# Sheet4.net
KiCad netlist of a schematic drawn in Altium Designer
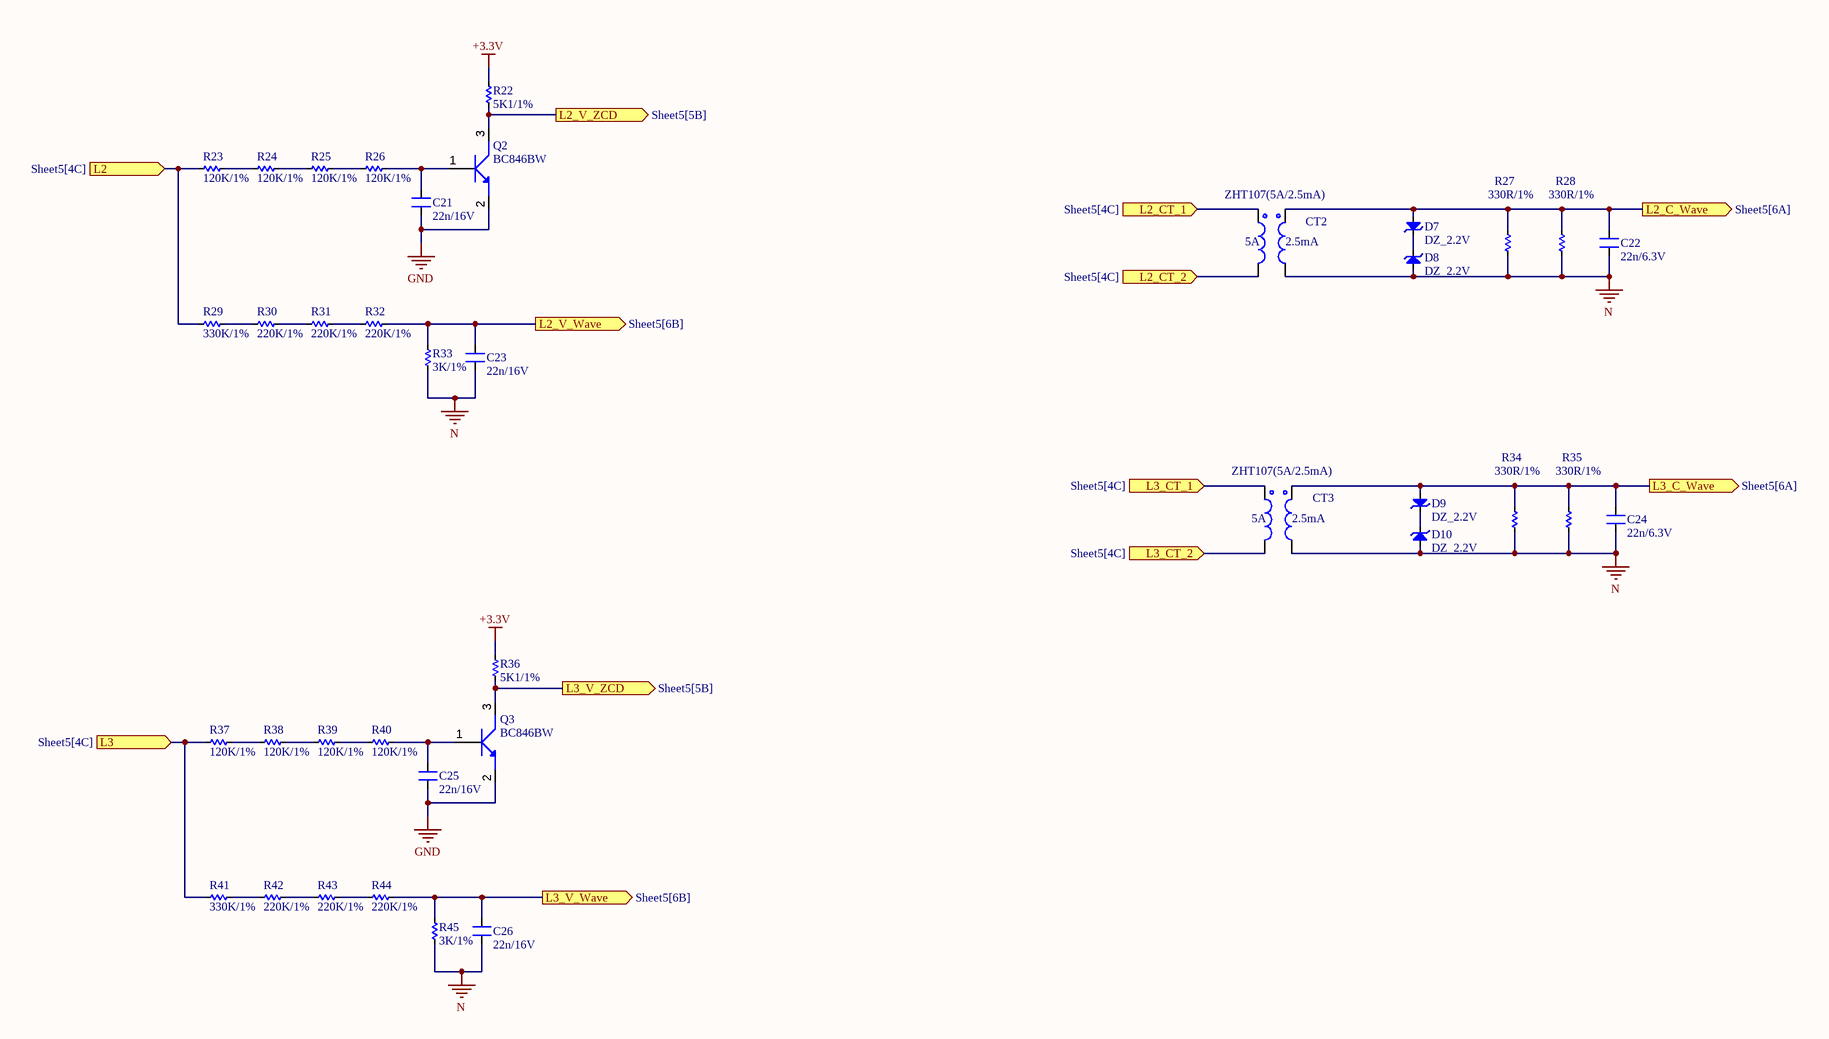
[diagram p0: Sheet4.SchDoc]

(export (version "E")
  (design (tool "Eeschema 10.0.6"))
  (components
    (comp (ref "C21")
      (value "22n/16V")
      (footprint "CAP_C_2012X110")
      (libsource (lib "DAK_Altium_Integrated_Lib") (part "CAP_SMD"))
    )
    (comp (ref "C22")
      (value "22n/6.3V")
      (footprint "CAP_C_2012X110")
      (libsource (lib "DAK_Altium_Integrated_Lib") (part "CAP_SMD"))
    )
    (comp (ref "C23")
      (value "22n/16V")
      (footprint "CAP_C_2012X110")
      (libsource (lib "DAK_Altium_Integrated_Lib") (part "CAP_SMD"))
    )
    (comp (ref "C24")
      (value "22n/6.3V")
      (footprint "CAP_C_2012X110")
      (libsource (lib "DAK_Altium_Integrated_Lib") (part "CAP_SMD"))
    )
    (comp (ref "C25")
      (value "22n/16V")
      (footprint "CAP_C_2012X110")
      (libsource (lib "DAK_Altium_Integrated_Lib") (part "CAP_SMD"))
    )
    (comp (ref "C26")
      (value "22n/16V")
      (footprint "CAP_C_2012X110")
      (libsource (lib "DAK_Altium_Integrated_Lib") (part "CAP_SMD"))
    )
    (comp (ref "CT2")
      (value "ZHT107(5A/2.5mA)")
      (footprint "ZHT107")
      (description "C5183046")
      (libsource (lib "PowerMeter") (part "ZHT-107"))
    )
    (comp (ref "CT3")
      (value "ZHT107(5A/2.5mA)")
      (footprint "ZHT107")
      (description "C5183046")
      (libsource (lib "PowerMeter") (part "ZHT-107"))
    )
    (comp (ref "D7")
      (value "DZ_2.2V")
      (footprint "LL-34")
      (description "Zenner")
      (libsource (lib "PowerMeter") (part "DIODE Zener"))
    )
    (comp (ref "D8")
      (value "DZ_2.2V")
      (footprint "LL-34")
      (description "Zenner")
      (libsource (lib "PowerMeter") (part "DIODE Zener"))
    )
    (comp (ref "D9")
      (value "DZ_2.2V")
      (footprint "LL-34")
      (description "Zenner")
      (libsource (lib "PowerMeter") (part "DIODE Zener"))
    )
    (comp (ref "D10")
      (value "DZ_2.2V")
      (footprint "LL-34")
      (description "Zenner")
      (libsource (lib "PowerMeter") (part "DIODE Zener"))
    )
    (comp (ref "Q2") (value "BC846BW") (footprint "SOT-323") (libsource (lib "PowerMeter") (part "BJT_NPN")))
    (comp (ref "Q3") (value "BC846BW") (footprint "SOT-323") (libsource (lib "PowerMeter") (part "BJT_NPN")))
    (comp (ref "R22")
      (value "5K1/1%")
      (footprint "RES_C_2012X65")
      (description "Resistor")
      (fields
        (field (name "MANUFACTURER") "Generic Components")
        (field (name "LCSC PART #") "C26023")
        (field (name "PUBLISHER") "Altium Hobart Technology Centre")
      )
      (libsource (lib "Library") (part "Res-SMD"))
    )
    (comp (ref "R23")
      (value "120K/1%")
      (footprint "RES_C_3216X70")
      (description "Resistor")
      (fields
        (field (name "MANUFACTURER") "Generic Components")
        (field (name "LCSC PART #") "C17908")
        (field (name "PUBLISHER") "Altium Hobart Technology Centre")
      )
      (libsource (lib "Library") (part "Res-SMD"))
    )
    (comp (ref "R24")
      (value "120K/1%")
      (footprint "RES_C_3216X70")
      (description "Resistor")
      (fields
        (field (name "MANUFACTURER") "Generic Components")
        (field (name "LCSC PART #") "C17908")
        (field (name "PUBLISHER") "Altium Hobart Technology Centre")
      )
      (libsource (lib "Library") (part "Res-SMD"))
    )
    (comp (ref "R25")
      (value "120K/1%")
      (footprint "RES_C_3216X70")
      (description "Resistor")
      (fields
        (field (name "MANUFACTURER") "Generic Components")
        (field (name "LCSC PART #") "C17908")
        (field (name "PUBLISHER") "Altium Hobart Technology Centre")
      )
      (libsource (lib "Library") (part "Res-SMD"))
    )
    (comp (ref "R26")
      (value "120K/1%")
      (footprint "RES_C_3216X70")
      (description "Resistor")
      (fields
        (field (name "MANUFACTURER") "Generic Components")
        (field (name "LCSC PART #") "C17908")
        (field (name "PUBLISHER") "Altium Hobart Technology Centre")
      )
      (libsource (lib "Library") (part "Res-SMD"))
    )
    (comp (ref "R27")
      (value "330R/1%")
      (footprint "RES_C_3216X70")
      (description "Resistor")
      (fields
        (field (name "MANUFACTURER") "Generic Components")
        (field (name "LCSC PART #") "C912714")
        (field (name "PUBLISHER") "Altium Hobart Technology Centre")
      )
      (libsource (lib "Library") (part "Res-SMD"))
    )
    (comp (ref "R28")
      (value "330R/1%")
      (footprint "RES_C_3216X70")
      (description "Resistor")
      (fields
        (field (name "MANUFACTURER") "Generic Components")
        (field (name "LCSC PART #") "C912714")
        (field (name "PUBLISHER") "Altium Hobart Technology Centre")
      )
      (libsource (lib "Library") (part "Res-SMD"))
    )
    (comp (ref "R29")
      (value "330K/1%")
      (footprint "RES_C_3216X70")
      (description "Resistor")
      (fields
        (field (name "MANUFACTURER") "Generic Components")
        (field (name "LCSC PART #") "C17929")
        (field (name "PUBLISHER") "Altium Hobart Technology Centre")
      )
      (libsource (lib "Library") (part "Res-SMD"))
    )
    (comp (ref "R30")
      (value "220K/1%")
      (footprint "RES_C_3216X70")
      (description "Resistor")
      (fields
        (field (name "MANUFACTURER") "Generic Components")
        (field (name "LCSC PART #") "C17956")
        (field (name "PUBLISHER") "Altium Hobart Technology Centre")
      )
      (libsource (lib "Library") (part "Res-SMD"))
    )
    (comp (ref "R31")
      (value "220K/1%")
      (footprint "RES_C_3216X70")
      (description "Resistor")
      (fields
        (field (name "MANUFACTURER") "Generic Components")
        (field (name "LCSC PART #") "C17956")
        (field (name "PUBLISHER") "Altium Hobart Technology Centre")
      )
      (libsource (lib "Library") (part "Res-SMD"))
    )
    (comp (ref "R32")
      (value "220K/1%")
      (footprint "RES_C_3216X70")
      (description "Resistor")
      (fields
        (field (name "MANUFACTURER") "Generic Components")
        (field (name "LCSC PART #") "C17956")
        (field (name "PUBLISHER") "Altium Hobart Technology Centre")
      )
      (libsource (lib "Library") (part "Res-SMD"))
    )
    (comp (ref "R33")
      (value "3K/1%")
      (footprint "RES_C_2012X65")
      (description "Resistor")
      (fields
        (field (name "MANUFACTURER") "Generic Components")
        (field (name "LCSC PART #") "C212458")
        (field (name "PUBLISHER") "Altium Hobart Technology Centre")
      )
      (libsource (lib "Library") (part "Res-SMD"))
    )
    (comp (ref "R34")
      (value "330R/1%")
      (footprint "RES_C_3216X70")
      (description "Resistor")
      (fields
        (field (name "MANUFACTURER") "Generic Components")
        (field (name "LCSC PART #") "C912714")
        (field (name "PUBLISHER") "Altium Hobart Technology Centre")
      )
      (libsource (lib "Library") (part "Res-SMD"))
    )
    (comp (ref "R35")
      (value "330R/1%")
      (footprint "RES_C_3216X70")
      (description "Resistor")
      (fields
        (field (name "MANUFACTURER") "Generic Components")
        (field (name "LCSC PART #") "C912714")
        (field (name "PUBLISHER") "Altium Hobart Technology Centre")
      )
      (libsource (lib "Library") (part "Res-SMD"))
    )
    (comp (ref "R36")
      (value "5K1/1%")
      (footprint "RES_C_2012X65")
      (description "Resistor")
      (fields
        (field (name "MANUFACTURER") "Generic Components")
        (field (name "LCSC PART #") "C26023")
        (field (name "PUBLISHER") "Altium Hobart Technology Centre")
      )
      (libsource (lib "Library") (part "Res-SMD"))
    )
    (comp (ref "R37")
      (value "120K/1%")
      (footprint "RES_C_3216X70")
      (description "Resistor")
      (fields
        (field (name "MANUFACTURER") "Generic Components")
        (field (name "LCSC PART #") "C17908")
        (field (name "PUBLISHER") "Altium Hobart Technology Centre")
      )
      (libsource (lib "Library") (part "Res-SMD"))
    )
    (comp (ref "R38")
      (value "120K/1%")
      (footprint "RES_C_3216X70")
      (description "Resistor")
      (fields
        (field (name "MANUFACTURER") "Generic Components")
        (field (name "LCSC PART #") "C17908")
        (field (name "PUBLISHER") "Altium Hobart Technology Centre")
      )
      (libsource (lib "Library") (part "Res-SMD"))
    )
    (comp (ref "R39")
      (value "120K/1%")
      (footprint "RES_C_3216X70")
      (description "Resistor")
      (fields
        (field (name "MANUFACTURER") "Generic Components")
        (field (name "LCSC PART #") "C17908")
        (field (name "PUBLISHER") "Altium Hobart Technology Centre")
      )
      (libsource (lib "Library") (part "Res-SMD"))
    )
    (comp (ref "R40")
      (value "120K/1%")
      (footprint "RES_C_3216X70")
      (description "Resistor")
      (fields
        (field (name "MANUFACTURER") "Generic Components")
        (field (name "LCSC PART #") "C17908")
        (field (name "PUBLISHER") "Altium Hobart Technology Centre")
      )
      (libsource (lib "Library") (part "Res-SMD"))
    )
    (comp (ref "R41")
      (value "330K/1%")
      (footprint "RES_C_3216X70")
      (description "Resistor")
      (fields
        (field (name "MANUFACTURER") "Generic Components")
        (field (name "LCSC PART #") "C17929")
        (field (name "PUBLISHER") "Altium Hobart Technology Centre")
      )
      (libsource (lib "Library") (part "Res-SMD"))
    )
    (comp (ref "R42")
      (value "220K/1%")
      (footprint "RES_C_3216X70")
      (description "Resistor")
      (fields
        (field (name "MANUFACTURER") "Generic Components")
        (field (name "LCSC PART #") "C17956")
        (field (name "PUBLISHER") "Altium Hobart Technology Centre")
      )
      (libsource (lib "Library") (part "Res-SMD"))
    )
    (comp (ref "R43")
      (value "220K/1%")
      (footprint "RES_C_3216X70")
      (description "Resistor")
      (fields
        (field (name "MANUFACTURER") "Generic Components")
        (field (name "LCSC PART #") "C17956")
        (field (name "PUBLISHER") "Altium Hobart Technology Centre")
      )
      (libsource (lib "Library") (part "Res-SMD"))
    )
    (comp (ref "R44")
      (value "220K/1%")
      (footprint "RES_C_3216X70")
      (description "Resistor")
      (fields
        (field (name "MANUFACTURER") "Generic Components")
        (field (name "LCSC PART #") "C17956")
        (field (name "PUBLISHER") "Altium Hobart Technology Centre")
      )
      (libsource (lib "Library") (part "Res-SMD"))
    )
    (comp (ref "R45")
      (value "3K/1%")
      (footprint "RES_C_2012X65")
      (description "Resistor")
      (fields
        (field (name "MANUFACTURER") "Generic Components")
        (field (name "LCSC PART #") "C212458")
        (field (name "PUBLISHER") "Altium Hobart Technology Centre")
      )
      (libsource (lib "Library") (part "Res-SMD"))
    )
  )
  (nets
    (net (code "1") (name "+3.3V") (class "Default")
      (node (ref "R22") (pin "1") (pinfunction "1_1") (pintype "passive"))
      (node (ref "R36") (pin "1") (pinfunction "1_1") (pintype "passive"))
    )
    (net (code "2") (name "/L2") (class "Default")
      (node (ref "R23") (pin "2") (pinfunction "2_2") (pintype "passive"))
      (node (ref "R29") (pin "2") (pinfunction "2_2") (pintype "passive"))
    )
    (net (code "3") (name "/L2_CT_1") (class "Default")
      (node (ref "CT2") (pin "1") (pinfunction "1_1") (pintype "passive"))
    )
    (net (code "4") (name "/L2_CT_2") (class "Default")
      (node (ref "CT2") (pin "2") (pinfunction "2_2") (pintype "passive"))
    )
    (net (code "5") (name "/L2_C_Wave") (class "Default")
      (node (ref "C22") (pin "2") (pinfunction "2_2") (pintype "passive"))
      (node (ref "CT2") (pin "3") (pinfunction "3_3") (pintype "passive"))
      (node (ref "D7") (pin "2") (pinfunction "A_2") (pintype "passive"))
      (node (ref "R27") (pin "1") (pinfunction "1_1") (pintype "passive"))
      (node (ref "R28") (pin "1") (pinfunction "1_1") (pintype "passive"))
    )
    (net (code "6") (name "/L2_V_Wave") (class "Default")
      (node (ref "C23") (pin "2") (pinfunction "2_2") (pintype "passive"))
      (node (ref "R32") (pin "1") (pinfunction "1_1") (pintype "passive"))
      (node (ref "R33") (pin "1") (pinfunction "1_1") (pintype "passive"))
    )
    (net (code "7") (name "/L2_V_ZCD") (class "Default")
      (node (ref "Q2") (pin "3") (pinfunction "C_3") (pintype "passive"))
      (node (ref "R22") (pin "2") (pinfunction "2_2") (pintype "passive"))
    )
    (net (code "8") (name "/L3") (class "Default")
      (node (ref "R37") (pin "2") (pinfunction "2_2") (pintype "passive"))
      (node (ref "R41") (pin "2") (pinfunction "2_2") (pintype "passive"))
    )
    (net (code "9") (name "/L3_CT_1") (class "Default")
      (node (ref "CT3") (pin "1") (pinfunction "1_1") (pintype "passive"))
    )
    (net (code "10") (name "/L3_CT_2") (class "Default")
      (node (ref "CT3") (pin "2") (pinfunction "2_2") (pintype "passive"))
    )
    (net (code "11") (name "/L3_C_Wave") (class "Default")
      (node (ref "C24") (pin "2") (pinfunction "2_2") (pintype "passive"))
      (node (ref "CT3") (pin "3") (pinfunction "3_3") (pintype "passive"))
      (node (ref "D9") (pin "2") (pinfunction "A_2") (pintype "passive"))
      (node (ref "R34") (pin "1") (pinfunction "1_1") (pintype "passive"))
      (node (ref "R35") (pin "1") (pinfunction "1_1") (pintype "passive"))
    )
    (net (code "12") (name "/L3_V_Wave") (class "Default")
      (node (ref "C26") (pin "2") (pinfunction "2_2") (pintype "passive"))
      (node (ref "R44") (pin "1") (pinfunction "1_1") (pintype "passive"))
      (node (ref "R45") (pin "1") (pinfunction "1_1") (pintype "passive"))
    )
    (net (code "13") (name "/L3_V_ZCD") (class "Default")
      (node (ref "Q3") (pin "3") (pinfunction "C_3") (pintype "passive"))
      (node (ref "R36") (pin "2") (pinfunction "2_2") (pintype "passive"))
    )
    (net (code "14") (name "GND") (class "Default")
      (node (ref "C21") (pin "1") (pinfunction "1_1") (pintype "passive"))
      (node (ref "C25") (pin "1") (pinfunction "1_1") (pintype "passive"))
      (node (ref "Q2") (pin "2") (pinfunction "E_2") (pintype "passive"))
      (node (ref "Q3") (pin "2") (pinfunction "E_2") (pintype "passive"))
    )
    (net (code "15") (name "N") (class "Default")
      (node (ref "C22") (pin "1") (pinfunction "1_1") (pintype "passive"))
      (node (ref "C23") (pin "1") (pinfunction "1_1") (pintype "passive"))
      (node (ref "C24") (pin "1") (pinfunction "1_1") (pintype "passive"))
      (node (ref "C26") (pin "1") (pinfunction "1_1") (pintype "passive"))
      (node (ref "CT2") (pin "4") (pinfunction "4_4") (pintype "passive"))
      (node (ref "CT3") (pin "4") (pinfunction "4_4") (pintype "passive"))
      (node (ref "D10") (pin "2") (pinfunction "A_2") (pintype "passive"))
      (node (ref "D8") (pin "2") (pinfunction "A_2") (pintype "passive"))
      (node (ref "R27") (pin "2") (pinfunction "2_2") (pintype "passive"))
      (node (ref "R28") (pin "2") (pinfunction "2_2") (pintype "passive"))
      (node (ref "R33") (pin "2") (pinfunction "2_2") (pintype "passive"))
      (node (ref "R34") (pin "2") (pinfunction "2_2") (pintype "passive"))
      (node (ref "R35") (pin "2") (pinfunction "2_2") (pintype "passive"))
      (node (ref "R45") (pin "2") (pinfunction "2_2") (pintype "passive"))
    )
    (net (code "16") (name "Net-(D7-K)") (class "Default")
      (node (ref "D7") (pin "1") (pinfunction "K_1") (pintype "passive"))
      (node (ref "D8") (pin "1") (pinfunction "K_1") (pintype "passive"))
    )
    (net (code "17") (name "Net-(D10-K)") (class "Default")
      (node (ref "D10") (pin "1") (pinfunction "K_1") (pintype "passive"))
      (node (ref "D9") (pin "1") (pinfunction "K_1") (pintype "passive"))
    )
    (net (code "18") (name "Net-(Q2-B)") (class "Default")
      (node (ref "C21") (pin "2") (pinfunction "2_2") (pintype "passive"))
      (node (ref "Q2") (pin "1") (pinfunction "B_1") (pintype "passive"))
      (node (ref "R26") (pin "1") (pinfunction "1_1") (pintype "passive"))
    )
    (net (code "19") (name "Net-(Q3-B)") (class "Default")
      (node (ref "C25") (pin "2") (pinfunction "2_2") (pintype "passive"))
      (node (ref "Q3") (pin "1") (pinfunction "B_1") (pintype "passive"))
      (node (ref "R40") (pin "1") (pinfunction "1_1") (pintype "passive"))
    )
    (net (code "20") (name "Net-(R23-Pad1)") (class "Default")
      (node (ref "R23") (pin "1") (pinfunction "1_1") (pintype "passive"))
      (node (ref "R24") (pin "2") (pinfunction "2_2") (pintype "passive"))
    )
    (net (code "21") (name "Net-(R24-Pad1)") (class "Default")
      (node (ref "R24") (pin "1") (pinfunction "1_1") (pintype "passive"))
      (node (ref "R25") (pin "2") (pinfunction "2_2") (pintype "passive"))
    )
    (net (code "22") (name "Net-(R25-Pad1)") (class "Default")
      (node (ref "R25") (pin "1") (pinfunction "1_1") (pintype "passive"))
      (node (ref "R26") (pin "2") (pinfunction "2_2") (pintype "passive"))
    )
    (net (code "23") (name "Net-(R29-Pad1)") (class "Default")
      (node (ref "R29") (pin "1") (pinfunction "1_1") (pintype "passive"))
      (node (ref "R30") (pin "2") (pinfunction "2_2") (pintype "passive"))
    )
    (net (code "24") (name "Net-(R30-Pad1)") (class "Default")
      (node (ref "R30") (pin "1") (pinfunction "1_1") (pintype "passive"))
      (node (ref "R31") (pin "2") (pinfunction "2_2") (pintype "passive"))
    )
    (net (code "25") (name "Net-(R31-Pad1)") (class "Default")
      (node (ref "R31") (pin "1") (pinfunction "1_1") (pintype "passive"))
      (node (ref "R32") (pin "2") (pinfunction "2_2") (pintype "passive"))
    )
    (net (code "26") (name "Net-(R37-Pad1)") (class "Default")
      (node (ref "R37") (pin "1") (pinfunction "1_1") (pintype "passive"))
      (node (ref "R38") (pin "2") (pinfunction "2_2") (pintype "passive"))
    )
    (net (code "27") (name "Net-(R38-Pad1)") (class "Default")
      (node (ref "R38") (pin "1") (pinfunction "1_1") (pintype "passive"))
      (node (ref "R39") (pin "2") (pinfunction "2_2") (pintype "passive"))
    )
    (net (code "28") (name "Net-(R39-Pad1)") (class "Default")
      (node (ref "R39") (pin "1") (pinfunction "1_1") (pintype "passive"))
      (node (ref "R40") (pin "2") (pinfunction "2_2") (pintype "passive"))
    )
    (net (code "29") (name "Net-(R41-Pad1)") (class "Default")
      (node (ref "R41") (pin "1") (pinfunction "1_1") (pintype "passive"))
      (node (ref "R42") (pin "2") (pinfunction "2_2") (pintype "passive"))
    )
    (net (code "30") (name "Net-(R42-Pad1)") (class "Default")
      (node (ref "R42") (pin "1") (pinfunction "1_1") (pintype "passive"))
      (node (ref "R43") (pin "2") (pinfunction "2_2") (pintype "passive"))
    )
    (net (code "31") (name "Net-(R43-Pad1)") (class "Default")
      (node (ref "R43") (pin "1") (pinfunction "1_1") (pintype "passive"))
      (node (ref "R44") (pin "2") (pinfunction "2_2") (pintype "passive"))
    )
  )
)
